# Strip-Con_board.net
KiCad netlist of a schematic drawn in EAGLE
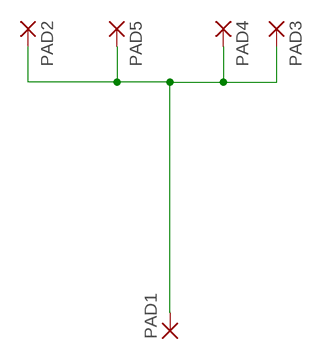
[diagram p0: schematic, sheet 1]

(export (version "E")
  (design (tool "Eeschema 10.0.6"))
  (components
    (comp (ref "PAD1")
      (value "SMD5")
      (footprint "eagle-import:SMD2,54-5,08")
      (libsource (lib "eagle-import") (part "SMD5"))
    )
    (comp (ref "PAD2")
      (value "SMD5")
      (footprint "eagle-import:SMD2,54-5,08")
      (libsource (lib "eagle-import") (part "SMD5"))
    )
    (comp (ref "PAD3")
      (value "SMD5")
      (footprint "eagle-import:SMD2,54-5,08")
      (libsource (lib "eagle-import") (part "SMD5"))
    )
    (comp (ref "PAD4")
      (value "SMD5")
      (footprint "eagle-import:SMD2,54-5,08")
      (libsource (lib "eagle-import") (part "SMD5"))
    )
    (comp (ref "PAD5")
      (value "SMD5")
      (footprint "eagle-import:SMD2,54-5,08")
      (libsource (lib "eagle-import") (part "SMD5"))
    )
  )
  (nets
    (net (code "1") (name "Net-(PAD1-P)") (class "Default")
      (node (ref "PAD1") (pin "1") (pinfunction "P_1") (pintype "passive"))
      (node (ref "PAD2") (pin "1") (pinfunction "P_1") (pintype "passive"))
      (node (ref "PAD3") (pin "1") (pinfunction "P_1") (pintype "passive"))
      (node (ref "PAD4") (pin "1") (pinfunction "P_1") (pintype "passive"))
      (node (ref "PAD5") (pin "1") (pinfunction "P_1") (pintype "passive"))
    )
  )
)
